# CC-S06-V00-DigitalIn.net
KiCad netlist of a schematic drawn in Altium Designer
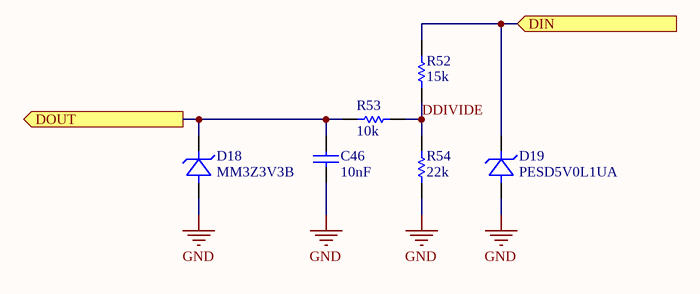
[diagram p0: CC-S06-V00-DigitalIn.SchDoc]

(export (version "E")
  (design (tool "Eeschema 10.0.6"))
  (components
    (comp (ref "C46")
      (value "10nF")
      (footprint "Cap_Ceramic_0603")
      (description "Capacitor, Ceramic, SMD, 10nF, 50V, 5%, X7R, 0603")
      (libsource (lib "StandardCapacitors") (part "10nF 50V 5% X7R 0603"))
    )
    (comp (ref "D18")
      (value "MM3Z3V3B")
      (footprint "SOD323F")
      (description "Diode, SMD, Zenner, 3.3V, 2%, 410mW, SOD-323F")
      (libsource (lib "QUTMS_DiodeLibrary") (part "MM3Z3V3B"))
    )
    (comp (ref "D19")
      (value "PESD5V0L1UA")
      (footprint "SOD323F")
      (description "12V Clamp 3.5A (8/20µs) Ipp Tvs Diode Surface Mount SOD-323")
      (libsource (lib "QUTMS_DiodeLibrary") (part "PESD5V0L1UA"))
    )
    (comp (ref "R52")
      (value "15k")
      (footprint "Res_ThinFilm_0603")
      (description "Resistor, SMD, 15k, 0.1W, 5%, 0603")
      (libsource (lib "StandardResistors") (part "15k 5% 0603"))
    )
    (comp (ref "R53")
      (value "10k")
      (footprint "Res_ThinFilm_0603")
      (description "Resistor, SMD, 10k, 0.1W, 5%, 0603")
      (libsource (lib "StandardResistors") (part "10k 5% 0603"))
    )
    (comp (ref "R54")
      (value "22k")
      (footprint "Res_ThinFilm_0603")
      (description "Resistor, SMD, 22k, 0.1W, 5%, 0603")
      (libsource (lib "StandardResistors") (part "22k 5% 0603"))
    )
  )
  (nets
    (net (code "1") (name "/DDIVIDE") (class "Default")
      (node (ref "R52") (pin "1") (pinfunction "1_1") (pintype "passive"))
      (node (ref "R53") (pin "2") (pinfunction "2_2") (pintype "passive"))
      (node (ref "R54") (pin "2") (pinfunction "2_2") (pintype "passive"))
    )
    (net (code "2") (name "/DIN") (class "Default")
      (node (ref "D19") (pin "K") (pinfunction "Cathode_K") (pintype "passive"))
      (node (ref "R52") (pin "2") (pinfunction "2_2") (pintype "passive"))
    )
    (net (code "3") (name "/DOUT") (class "Default")
      (node (ref "C46") (pin "2") (pinfunction "2_2") (pintype "passive"))
      (node (ref "D18") (pin "K") (pinfunction "Cathode_K") (pintype "passive"))
      (node (ref "R53") (pin "1") (pinfunction "1_1") (pintype "passive"))
    )
    (net (code "4") (name "GND") (class "Default")
      (node (ref "C46") (pin "1") (pinfunction "1_1") (pintype "passive"))
      (node (ref "D18") (pin "A") (pinfunction "Anode_A") (pintype "passive"))
      (node (ref "D19") (pin "A") (pinfunction "Anode_A") (pintype "passive"))
      (node (ref "R54") (pin "1") (pinfunction "1_1") (pintype "passive"))
    )
  )
)
